# Dual-suuply.net
KiCad netlist of a schematic drawn in EAGLE
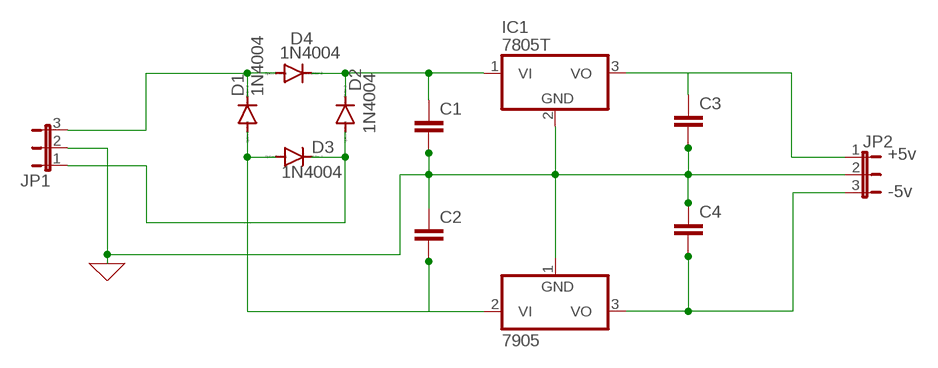
[diagram p0: schematic, sheet 1]

(export (version "E")
  (design (tool "Eeschema 10.0.6"))
  (components
    (comp (ref "7905")
      (value "7906T")
      (footprint "eagle-import:TO220H")
      (libsource (lib "eagle-import") (part "79T06"))
    )
    (comp (ref "C1")
      (value "C-EU025-024X044")
      (footprint "eagle-import:C025-024X044")
      (libsource (lib "eagle-import") (part "C-EU025-024X044"))
    )
    (comp (ref "C2")
      (value "C-EU025-024X044")
      (footprint "eagle-import:C025-024X044")
      (libsource (lib "eagle-import") (part "C-EU025-024X044"))
    )
    (comp (ref "C3")
      (value "C-EU025-024X044")
      (footprint "eagle-import:C025-024X044")
      (libsource (lib "eagle-import") (part "C-EU025-024X044"))
    )
    (comp (ref "C4")
      (value "C-EU025-024X044")
      (footprint "eagle-import:C025-024X044")
      (libsource (lib "eagle-import") (part "C-EU025-024X044"))
    )
    (comp (ref "D1")
      (value "1N4004")
      (footprint "eagle-import:DO41-10")
      (libsource (lib "eagle-import") (part "1N4004"))
    )
    (comp (ref "D2")
      (value "1N4004")
      (footprint "eagle-import:DO41-10")
      (libsource (lib "eagle-import") (part "1N4004"))
    )
    (comp (ref "D3")
      (value "1N4004")
      (footprint "eagle-import:DO41-10")
      (libsource (lib "eagle-import") (part "1N4004"))
    )
    (comp (ref "D4")
      (value "1N4004")
      (footprint "eagle-import:DO41-10")
      (libsource (lib "eagle-import") (part "1N4004"))
    )
    (comp (ref "IC1")
      (value "7805T")
      (footprint "eagle-import:TO220H")
      (libsource (lib "eagle-import") (part "78T05"))
    )
    (comp (ref "JP1")
      (value "JP2E")
      (footprint "eagle-import:JP2")
      (libsource (lib "eagle-import") (part "JP2E"))
    )
    (comp (ref "JP2")
      (value "JP2E")
      (footprint "eagle-import:JP2")
      (libsource (lib "eagle-import") (part "JP2E"))
    )
  )
  (nets
    (net (code "1") (name "GND") (class "Default")
      (node (ref "7905") (pin "1") (pinfunction "GND_1") (pintype "passive"))
      (node (ref "C1") (pin "2") (pinfunction "2_2") (pintype "passive"))
      (node (ref "C2") (pin "1") (pinfunction "1_1") (pintype "passive"))
      (node (ref "C3") (pin "2") (pinfunction "2_2") (pintype "passive"))
      (node (ref "C4") (pin "1") (pinfunction "1_1") (pintype "passive"))
      (node (ref "IC1") (pin "2") (pinfunction "GND_2") (pintype "passive"))
      (node (ref "JP1") (pin "2") (pinfunction "2_2") (pintype "passive"))
      (node (ref "JP2") (pin "2") (pinfunction "2_2") (pintype "passive"))
    )
    (net (code "2") (name "Net-(7905-VI)") (class "Default")
      (node (ref "7905") (pin "2") (pinfunction "VI_2") (pintype "input"))
      (node (ref "C2") (pin "2") (pinfunction "2_2") (pintype "passive"))
      (node (ref "D1") (pin "A") (pinfunction "A_A") (pintype "passive"))
      (node (ref "D3") (pin "A") (pinfunction "A_A") (pintype "passive"))
    )
    (net (code "3") (name "Net-(7905-VO)") (class "Default")
      (node (ref "7905") (pin "3") (pinfunction "VO_3") (pintype "passive"))
      (node (ref "C4") (pin "2") (pinfunction "2_2") (pintype "passive"))
      (node (ref "JP2") (pin "3") (pinfunction "3_3") (pintype "passive"))
    )
    (net (code "4") (name "Net-(D1-PadC)") (class "Default")
      (node (ref "D1") (pin "C") (pinfunction "C_C") (pintype "passive"))
      (node (ref "D4") (pin "A") (pinfunction "A_A") (pintype "passive"))
      (node (ref "JP1") (pin "3") (pinfunction "3_3") (pintype "passive"))
    )
    (net (code "5") (name "Net-(D2-PadA)") (class "Default")
      (node (ref "D2") (pin "A") (pinfunction "A_A") (pintype "passive"))
      (node (ref "D3") (pin "C") (pinfunction "C_C") (pintype "passive"))
      (node (ref "JP1") (pin "1") (pinfunction "1_1") (pintype "passive"))
    )
    (net (code "6") (name "Net-(IC1-VI)") (class "Default")
      (node (ref "C1") (pin "1") (pinfunction "1_1") (pintype "passive"))
      (node (ref "D2") (pin "C") (pinfunction "C_C") (pintype "passive"))
      (node (ref "D4") (pin "C") (pinfunction "C_C") (pintype "passive"))
      (node (ref "IC1") (pin "1") (pinfunction "VI_1") (pintype "input"))
    )
    (net (code "7") (name "Net-(IC1-VO)") (class "Default")
      (node (ref "C3") (pin "1") (pinfunction "1_1") (pintype "passive"))
      (node (ref "IC1") (pin "3") (pinfunction "VO_3") (pintype "passive"))
      (node (ref "JP2") (pin "1") (pinfunction "1_1") (pintype "passive"))
    )
  )
)
